# ALU.net
KiCad netlist of a schematic drawn in EAGLE
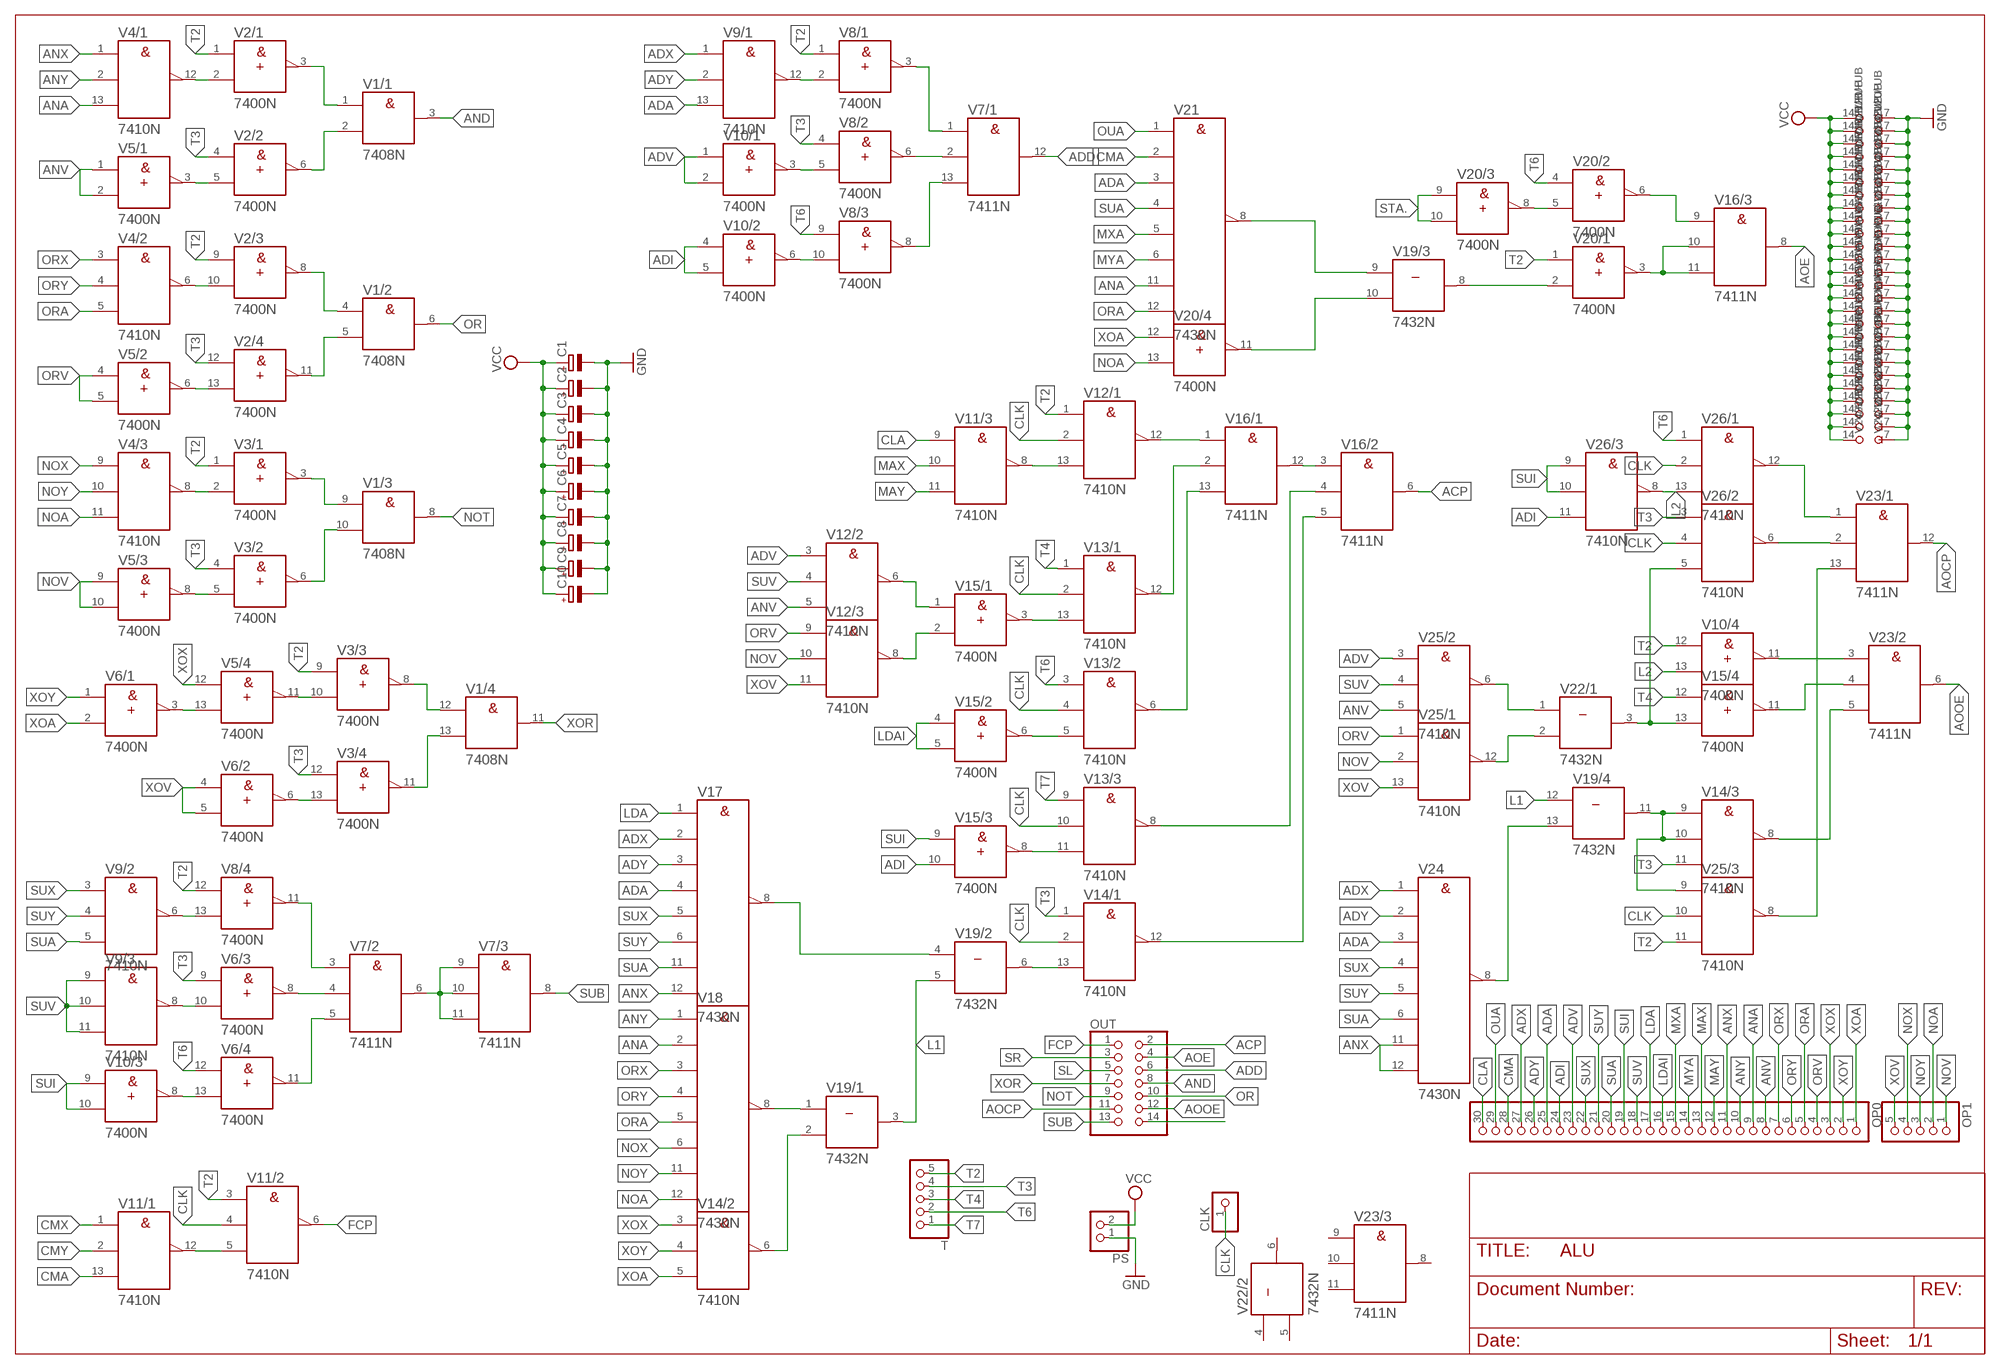
[diagram p0: schematic, sheet 1]

(export (version "E")
  (design (tool "Eeschema 10.0.6"))
  (components
    (comp (ref "C1")
      (value "CPOL-EUE2.5-6")
      (footprint "eagle-import:E2,5-6")
      (libsource (lib "eagle-import") (part "CPOL-EUE2.5-6"))
    )
    (comp (ref "C2")
      (value "CPOL-EUE2.5-6")
      (footprint "eagle-import:E2,5-6")
      (libsource (lib "eagle-import") (part "CPOL-EUE2.5-6"))
    )
    (comp (ref "C3")
      (value "CPOL-EUE2.5-6")
      (footprint "eagle-import:E2,5-6")
      (libsource (lib "eagle-import") (part "CPOL-EUE2.5-6"))
    )
    (comp (ref "C4")
      (value "CPOL-EUE2.5-6")
      (footprint "eagle-import:E2,5-6")
      (libsource (lib "eagle-import") (part "CPOL-EUE2.5-6"))
    )
    (comp (ref "C5")
      (value "CPOL-EUE2.5-6")
      (footprint "eagle-import:E2,5-6")
      (libsource (lib "eagle-import") (part "CPOL-EUE2.5-6"))
    )
    (comp (ref "C6")
      (value "CPOL-EUE2.5-6")
      (footprint "eagle-import:E2,5-6")
      (libsource (lib "eagle-import") (part "CPOL-EUE2.5-6"))
    )
    (comp (ref "C7")
      (value "CPOL-EUE2.5-6")
      (footprint "eagle-import:E2,5-6")
      (libsource (lib "eagle-import") (part "CPOL-EUE2.5-6"))
    )
    (comp (ref "C8")
      (value "CPOL-EUE2.5-6")
      (footprint "eagle-import:E2,5-6")
      (libsource (lib "eagle-import") (part "CPOL-EUE2.5-6"))
    )
    (comp (ref "C9")
      (value "CPOL-EUE2.5-6")
      (footprint "eagle-import:E2,5-6")
      (libsource (lib "eagle-import") (part "CPOL-EUE2.5-6"))
    )
    (comp (ref "C10")
      (value "CPOL-EUE2.5-6")
      (footprint "eagle-import:E2,5-6")
      (libsource (lib "eagle-import") (part "CPOL-EUE2.5-6"))
    )
    (comp (ref "CLK")
      (value "PINHD-1X1")
      (footprint "eagle-import:1X01")
      (libsource (lib "eagle-import") (part "PINHD-1X1"))
    )
    (comp (ref "OP0")
      (value "PINHD-1X30")
      (footprint "eagle-import:1X30")
      (libsource (lib "eagle-import") (part "PINHD-1X30"))
    )
    (comp (ref "OP1")
      (value "PINHD-1X5")
      (footprint "eagle-import:1X05")
      (libsource (lib "eagle-import") (part "PINHD-1X5"))
    )
    (comp (ref "OUT")
      (value "PINHD-2X7")
      (footprint "eagle-import:2X07")
      (libsource (lib "eagle-import") (part "PINHD-2X7"))
    )
    (comp (ref "PS")
      (value "PINHD-1X2")
      (footprint "eagle-import:1X02")
      (libsource (lib "eagle-import") (part "PINHD-1X2"))
    )
    (comp (ref "T")
      (value "PINHD-1X5")
      (footprint "eagle-import:1X05")
      (libsource (lib "eagle-import") (part "PINHD-1X5"))
    )
    (comp (ref "V1")
      (value "7408N")
      (footprint "eagle-import:DIL14")
      (libsource (lib "eagle-import") (part "7408N"))
    )
    (comp (ref "V2")
      (value "7400N")
      (footprint "eagle-import:DIL14")
      (libsource (lib "eagle-import") (part "7400N"))
    )
    (comp (ref "V3")
      (value "7400N")
      (footprint "eagle-import:DIL14")
      (libsource (lib "eagle-import") (part "7400N"))
    )
    (comp (ref "V4")
      (value "7410N")
      (footprint "eagle-import:DIL14")
      (libsource (lib "eagle-import") (part "7410N"))
    )
    (comp (ref "V5")
      (value "7400N")
      (footprint "eagle-import:DIL14")
      (libsource (lib "eagle-import") (part "7400N"))
    )
    (comp (ref "V6")
      (value "7400N")
      (footprint "eagle-import:DIL14")
      (libsource (lib "eagle-import") (part "7400N"))
    )
    (comp (ref "V7")
      (value "7411N")
      (footprint "eagle-import:DIL14")
      (libsource (lib "eagle-import") (part "7411N"))
    )
    (comp (ref "V8")
      (value "7400N")
      (footprint "eagle-import:DIL14")
      (libsource (lib "eagle-import") (part "7400N"))
    )
    (comp (ref "V9")
      (value "7410N")
      (footprint "eagle-import:DIL14")
      (libsource (lib "eagle-import") (part "7410N"))
    )
    (comp (ref "V10")
      (value "7400N")
      (footprint "eagle-import:DIL14")
      (libsource (lib "eagle-import") (part "7400N"))
    )
    (comp (ref "V11")
      (value "7410N")
      (footprint "eagle-import:DIL14")
      (libsource (lib "eagle-import") (part "7410N"))
    )
    (comp (ref "V12")
      (value "7410N")
      (footprint "eagle-import:DIL14")
      (libsource (lib "eagle-import") (part "7410N"))
    )
    (comp (ref "V13")
      (value "7410N")
      (footprint "eagle-import:DIL14")
      (libsource (lib "eagle-import") (part "7410N"))
    )
    (comp (ref "V14")
      (value "7410N")
      (footprint "eagle-import:DIL14")
      (libsource (lib "eagle-import") (part "7410N"))
    )
    (comp (ref "V15")
      (value "7400N")
      (footprint "eagle-import:DIL14")
      (libsource (lib "eagle-import") (part "7400N"))
    )
    (comp (ref "V16")
      (value "7411N")
      (footprint "eagle-import:DIL14")
      (libsource (lib "eagle-import") (part "7411N"))
    )
    (comp (ref "V17")
      (value "7430N")
      (footprint "eagle-import:DIL14")
      (libsource (lib "eagle-import") (part "7430N"))
    )
    (comp (ref "V18")
      (value "7430N")
      (footprint "eagle-import:DIL14")
      (libsource (lib "eagle-import") (part "7430N"))
    )
    (comp (ref "V19")
      (value "7432N")
      (footprint "eagle-import:DIL14")
      (libsource (lib "eagle-import") (part "7432N"))
    )
    (comp (ref "V20")
      (value "7400N")
      (footprint "eagle-import:DIL14")
      (libsource (lib "eagle-import") (part "7400N"))
    )
    (comp (ref "V21")
      (value "7430N")
      (footprint "eagle-import:DIL14")
      (libsource (lib "eagle-import") (part "7430N"))
    )
    (comp (ref "V22")
      (value "7432N")
      (footprint "eagle-import:DIL14")
      (libsource (lib "eagle-import") (part "7432N"))
    )
    (comp (ref "V23")
      (value "7411N")
      (footprint "eagle-import:DIL14")
      (libsource (lib "eagle-import") (part "7411N"))
    )
    (comp (ref "V24")
      (value "7430N")
      (footprint "eagle-import:DIL14")
      (libsource (lib "eagle-import") (part "7430N"))
    )
    (comp (ref "V25")
      (value "7410N")
      (footprint "eagle-import:DIL14")
      (libsource (lib "eagle-import") (part "7410N"))
    )
    (comp (ref "V26")
      (value "7410N")
      (footprint "eagle-import:DIL14")
      (libsource (lib "eagle-import") (part "7410N"))
    )
  )
  (nets
    (net (code "1") (name "ACP") (class "Default")
      (node (ref "OUT") (pin "2") (pinfunction "2_2") (pintype "passive"))
      (node (ref "V16") (pin "6") (pinfunction "Y_6") (pintype "output"))
    )
    (net (code "2") (name "ADA") (class "Default")
      (node (ref "OP0") (pin "25") (pinfunction "25_25") (pintype "passive"))
      (node (ref "V17") (pin "4") (pinfunction "D_4") (pintype "input"))
      (node (ref "V21") (pin "3") (pinfunction "C_3") (pintype "input"))
      (node (ref "V24") (pin "3") (pinfunction "C_3") (pintype "input"))
      (node (ref "V9") (pin "13") (pinfunction "C_13") (pintype "input"))
    )
    (net (code "3") (name "ADD") (class "Default")
      (node (ref "OUT") (pin "6") (pinfunction "6_6") (pintype "passive"))
      (node (ref "V7") (pin "12") (pinfunction "Y_12") (pintype "output"))
    )
    (net (code "4") (name "ADI") (class "Default")
      (node (ref "OP0") (pin "24") (pinfunction "24_24") (pintype "passive"))
      (node (ref "V10") (pin "4") (pinfunction "A_4") (pintype "input"))
      (node (ref "V10") (pin "5") (pinfunction "B_5") (pintype "input"))
      (node (ref "V15") (pin "10") (pinfunction "B_10") (pintype "input"))
      (node (ref "V26") (pin "11") (pinfunction "C_11") (pintype "input"))
    )
    (net (code "5") (name "ADV") (class "Default")
      (node (ref "OP0") (pin "23") (pinfunction "23_23") (pintype "passive"))
      (node (ref "V10") (pin "1") (pinfunction "A_1") (pintype "input"))
      (node (ref "V10") (pin "2") (pinfunction "B_2") (pintype "input"))
      (node (ref "V12") (pin "3") (pinfunction "A_3") (pintype "input"))
      (node (ref "V25") (pin "3") (pinfunction "A_3") (pintype "input"))
    )
    (net (code "6") (name "ADX") (class "Default")
      (node (ref "OP0") (pin "27") (pinfunction "27_27") (pintype "passive"))
      (node (ref "V17") (pin "2") (pinfunction "B_2") (pintype "input"))
      (node (ref "V24") (pin "1") (pinfunction "A_1") (pintype "input"))
      (node (ref "V9") (pin "1") (pinfunction "A_1") (pintype "input"))
    )
    (net (code "7") (name "ADY") (class "Default")
      (node (ref "OP0") (pin "26") (pinfunction "26_26") (pintype "passive"))
      (node (ref "V17") (pin "3") (pinfunction "C_3") (pintype "input"))
      (node (ref "V24") (pin "2") (pinfunction "B_2") (pintype "input"))
      (node (ref "V9") (pin "2") (pinfunction "B_2") (pintype "input"))
    )
    (net (code "8") (name "ANA") (class "Default")
      (node (ref "OP0") (pin "9") (pinfunction "9_9") (pintype "passive"))
      (node (ref "V18") (pin "2") (pinfunction "B_2") (pintype "input"))
      (node (ref "V21") (pin "11") (pinfunction "G_11") (pintype "input"))
      (node (ref "V4") (pin "13") (pinfunction "C_13") (pintype "input"))
    )
    (net (code "9") (name "AND") (class "Default")
      (node (ref "OUT") (pin "8") (pinfunction "8_8") (pintype "passive"))
      (node (ref "V1") (pin "3") (pinfunction "Y_3") (pintype "output"))
    )
    (net (code "10") (name "ANV") (class "Default")
      (node (ref "OP0") (pin "8") (pinfunction "8_8") (pintype "passive"))
      (node (ref "V12") (pin "5") (pinfunction "C_5") (pintype "input"))
      (node (ref "V25") (pin "5") (pinfunction "C_5") (pintype "input"))
      (node (ref "V5") (pin "1") (pinfunction "A_1") (pintype "input"))
      (node (ref "V5") (pin "2") (pinfunction "B_2") (pintype "input"))
    )
    (net (code "11") (name "ANX") (class "Default")
      (node (ref "OP0") (pin "11") (pinfunction "11_11") (pintype "passive"))
      (node (ref "V17") (pin "12") (pinfunction "H_12") (pintype "input"))
      (node (ref "V24") (pin "11") (pinfunction "G_11") (pintype "input"))
      (node (ref "V24") (pin "12") (pinfunction "H_12") (pintype "input"))
      (node (ref "V4") (pin "1") (pinfunction "A_1") (pintype "input"))
    )
    (net (code "12") (name "ANY") (class "Default")
      (node (ref "OP0") (pin "10") (pinfunction "10_10") (pintype "passive"))
      (node (ref "V18") (pin "1") (pinfunction "A_1") (pintype "input"))
      (node (ref "V4") (pin "2") (pinfunction "B_2") (pintype "input"))
    )
    (net (code "13") (name "AOCP") (class "Default")
      (node (ref "OUT") (pin "11") (pinfunction "11_11") (pintype "passive"))
      (node (ref "V23") (pin "12") (pinfunction "Y_12") (pintype "output"))
    )
    (net (code "14") (name "AOE") (class "Default")
      (node (ref "OUT") (pin "4") (pinfunction "4_4") (pintype "passive"))
      (node (ref "V16") (pin "8") (pinfunction "Y_8") (pintype "output"))
    )
    (net (code "15") (name "AOOE") (class "Default")
      (node (ref "OUT") (pin "12") (pinfunction "12_12") (pintype "passive"))
      (node (ref "V23") (pin "6") (pinfunction "Y_6") (pintype "output"))
    )
    (net (code "16") (name "CLA") (class "Default")
      (node (ref "OP0") (pin "30") (pinfunction "30_30") (pintype "passive"))
      (node (ref "V11") (pin "9") (pinfunction "A_9") (pintype "input"))
    )
    (net (code "17") (name "CLK") (class "Default")
      (node (ref "CLK") (pin "1") (pinfunction "1_1") (pintype "passive"))
      (node (ref "V11") (pin "4") (pinfunction "B_4") (pintype "input"))
      (node (ref "V12") (pin "2") (pinfunction "B_2") (pintype "input"))
      (node (ref "V13") (pin "10") (pinfunction "B_10") (pintype "input"))
      (node (ref "V13") (pin "2") (pinfunction "B_2") (pintype "input"))
      (node (ref "V13") (pin "4") (pinfunction "B_4") (pintype "input"))
      (node (ref "V14") (pin "2") (pinfunction "B_2") (pintype "input"))
      (node (ref "V25") (pin "10") (pinfunction "B_10") (pintype "input"))
      (node (ref "V26") (pin "2") (pinfunction "B_2") (pintype "input"))
      (node (ref "V26") (pin "4") (pinfunction "B_4") (pintype "input"))
    )
    (net (code "18") (name "CMA") (class "Default")
      (node (ref "OP0") (pin "28") (pinfunction "28_28") (pintype "passive"))
      (node (ref "V11") (pin "13") (pinfunction "C_13") (pintype "input"))
      (node (ref "V21") (pin "2") (pinfunction "B_2") (pintype "input"))
    )
    (net (code "19") (name "CMX") (class "Default")
      (node (ref "V11") (pin "1") (pinfunction "A_1") (pintype "input"))
    )
    (net (code "20") (name "CMY") (class "Default")
      (node (ref "V11") (pin "2") (pinfunction "B_2") (pintype "input"))
    )
    (net (code "21") (name "FCP") (class "Default")
      (node (ref "OUT") (pin "1") (pinfunction "1_1") (pintype "passive"))
      (node (ref "V11") (pin "6") (pinfunction "Y_6") (pintype "output"))
    )
    (net (code "22") (name "GND") (class "Default")
      (node (ref "C1") (pin "-") (pinfunction "-_-") (pintype "passive"))
      (node (ref "C10") (pin "-") (pinfunction "-_-") (pintype "passive"))
      (node (ref "C2") (pin "-") (pinfunction "-_-") (pintype "passive"))
      (node (ref "C3") (pin "-") (pinfunction "-_-") (pintype "passive"))
      (node (ref "C4") (pin "-") (pinfunction "-_-") (pintype "passive"))
      (node (ref "C5") (pin "-") (pinfunction "-_-") (pintype "passive"))
      (node (ref "C6") (pin "-") (pinfunction "-_-") (pintype "passive"))
      (node (ref "C7") (pin "-") (pinfunction "-_-") (pintype "passive"))
      (node (ref "C8") (pin "-") (pinfunction "-_-") (pintype "passive"))
      (node (ref "C9") (pin "-") (pinfunction "-_-") (pintype "passive"))
      (node (ref "PS") (pin "1") (pinfunction "1_1") (pintype "passive"))
      (node (ref "V1") (pin "7") (pinfunction "-UB_7") (pintype "power_in"))
      (node (ref "V10") (pin "7") (pinfunction "-UB_7") (pintype "power_in"))
      (node (ref "V11") (pin "7") (pinfunction "-UB_7") (pintype "power_in"))
      (node (ref "V12") (pin "7") (pinfunction "-UB_7") (pintype "power_in"))
      (node (ref "V13") (pin "7") (pinfunction "-UB_7") (pintype "power_in"))
      (node (ref "V14") (pin "7") (pinfunction "-UB_7") (pintype "power_in"))
      (node (ref "V15") (pin "7") (pinfunction "-UB_7") (pintype "power_in"))
      (node (ref "V16") (pin "7") (pinfunction "-UB_7") (pintype "power_in"))
      (node (ref "V17") (pin "7") (pinfunction "-UB_7") (pintype "power_in"))
      (node (ref "V18") (pin "7") (pinfunction "-UB_7") (pintype "power_in"))
      (node (ref "V19") (pin "7") (pinfunction "-UB_7") (pintype "power_in"))
      (node (ref "V2") (pin "7") (pinfunction "-UB_7") (pintype "power_in"))
      (node (ref "V20") (pin "7") (pinfunction "-UB_7") (pintype "power_in"))
      (node (ref "V21") (pin "7") (pinfunction "-UB_7") (pintype "power_in"))
      (node (ref "V22") (pin "7") (pinfunction "-UB_7") (pintype "power_in"))
      (node (ref "V23") (pin "7") (pinfunction "-UB_7") (pintype "power_in"))
      (node (ref "V24") (pin "7") (pinfunction "-UB_7") (pintype "power_in"))
      (node (ref "V25") (pin "7") (pinfunction "-UB_7") (pintype "power_in"))
      (node (ref "V26") (pin "7") (pinfunction "-UB_7") (pintype "power_in"))
      (node (ref "V3") (pin "7") (pinfunction "-UB_7") (pintype "power_in"))
      (node (ref "V4") (pin "7") (pinfunction "-UB_7") (pintype "power_in"))
      (node (ref "V5") (pin "7") (pinfunction "-UB_7") (pintype "power_in"))
      (node (ref "V6") (pin "7") (pinfunction "-UB_7") (pintype "power_in"))
      (node (ref "V7") (pin "7") (pinfunction "-UB_7") (pintype "power_in"))
      (node (ref "V8") (pin "7") (pinfunction "-UB_7") (pintype "power_in"))
      (node (ref "V9") (pin "7") (pinfunction "-UB_7") (pintype "power_in"))
    )
    (net (code "23") (name "L1") (class "Default")
      (node (ref "V19") (pin "12") (pinfunction "A_12") (pintype "input"))
      (node (ref "V19") (pin "3") (pinfunction "Y_3") (pintype "output"))
      (node (ref "V19") (pin "5") (pinfunction "B_5") (pintype "input"))
    )
    (net (code "24") (name "L2") (class "Default")
      (node (ref "V10") (pin "13") (pinfunction "B_13") (pintype "input"))
      (node (ref "V26") (pin "13") (pinfunction "C_13") (pintype "input"))
      (node (ref "V26") (pin "8") (pinfunction "Y_8") (pintype "output"))
    )
    (net (code "25") (name "LDA") (class "Default")
      (node (ref "OP0") (pin "17") (pinfunction "17_17") (pintype "passive"))
      (node (ref "V17") (pin "1") (pinfunction "A_1") (pintype "input"))
    )
    (net (code "26") (name "LDAI") (class "Default")
      (node (ref "OP0") (pin "16") (pinfunction "16_16") (pintype "passive"))
      (node (ref "V15") (pin "4") (pinfunction "A_4") (pintype "input"))
      (node (ref "V15") (pin "5") (pinfunction "B_5") (pintype "input"))
    )
    (net (code "27") (name "MAX") (class "Default")
      (node (ref "OP0") (pin "13") (pinfunction "13_13") (pintype "passive"))
      (node (ref "V11") (pin "10") (pinfunction "B_10") (pintype "input"))
    )
    (net (code "28") (name "MAY") (class "Default")
      (node (ref "OP0") (pin "12") (pinfunction "12_12") (pintype "passive"))
      (node (ref "V11") (pin "11") (pinfunction "C_11") (pintype "input"))
    )
    (net (code "29") (name "MXA") (class "Default")
      (node (ref "OP0") (pin "15") (pinfunction "15_15") (pintype "passive"))
      (node (ref "V21") (pin "5") (pinfunction "E_5") (pintype "input"))
    )
    (net (code "30") (name "MYA") (class "Default")
      (node (ref "OP0") (pin "14") (pinfunction "14_14") (pintype "passive"))
      (node (ref "V21") (pin "6") (pinfunction "F_6") (pintype "input"))
    )
    (net (code "31") (name "NOA") (class "Default")
      (node (ref "OP1") (pin "2") (pinfunction "2_2") (pintype "passive"))
      (node (ref "V18") (pin "12") (pinfunction "H_12") (pintype "input"))
      (node (ref "V20") (pin "13") (pinfunction "B_13") (pintype "input"))
      (node (ref "V4") (pin "11") (pinfunction "C_11") (pintype "input"))
    )
    (net (code "32") (name "NOT") (class "Default")
      (node (ref "OUT") (pin "9") (pinfunction "9_9") (pintype "passive"))
      (node (ref "V1") (pin "8") (pinfunction "Y_8") (pintype "output"))
    )
    (net (code "33") (name "NOV") (class "Default")
      (node (ref "OP1") (pin "1") (pinfunction "1_1") (pintype "passive"))
      (node (ref "V12") (pin "10") (pinfunction "B_10") (pintype "input"))
      (node (ref "V25") (pin "2") (pinfunction "B_2") (pintype "input"))
      (node (ref "V5") (pin "10") (pinfunction "B_10") (pintype "input"))
      (node (ref "V5") (pin "9") (pinfunction "A_9") (pintype "input"))
    )
    (net (code "34") (name "NOX") (class "Default")
      (node (ref "OP1") (pin "4") (pinfunction "4_4") (pintype "passive"))
      (node (ref "V18") (pin "6") (pinfunction "F_6") (pintype "input"))
      (node (ref "V4") (pin "9") (pinfunction "A_9") (pintype "input"))
    )
    (net (code "35") (name "NOY") (class "Default")
      (node (ref "OP1") (pin "3") (pinfunction "3_3") (pintype "passive"))
      (node (ref "V18") (pin "11") (pinfunction "G_11") (pintype "input"))
      (node (ref "V4") (pin "10") (pinfunction "B_10") (pintype "input"))
    )
    (net (code "36") (name "Net-(V1C-A)") (class "Default")
      (node (ref "V1") (pin "1") (pinfunction "A_1") (pintype "input"))
      (node (ref "V2") (pin "3") (pinfunction "Y_3") (pintype "output"))
    )
    (net (code "37") (name "Net-(V1C-B)") (class "Default")
      (node (ref "V1") (pin "2") (pinfunction "B_2") (pintype "input"))
      (node (ref "V2") (pin "6") (pinfunction "Y_6") (pintype "output"))
    )
    (net (code "38") (name "Net-(V1D-A)") (class "Default")
      (node (ref "V1") (pin "4") (pinfunction "A_4") (pintype "input"))
      (node (ref "V2") (pin "8") (pinfunction "Y_8") (pintype "output"))
    )
    (net (code "39") (name "Net-(V1D-B)") (class "Default")
      (node (ref "V1") (pin "5") (pinfunction "B_5") (pintype "input"))
      (node (ref "V2") (pin "11") (pinfunction "Y_11") (pintype "output"))
    )
    (net (code "40") (name "Net-(V1E-A)") (class "Default")
      (node (ref "V1") (pin "9") (pinfunction "A_9") (pintype "input"))
      (node (ref "V3") (pin "3") (pinfunction "Y_3") (pintype "output"))
    )
    (net (code "41") (name "Net-(V1E-B)") (class "Default")
      (node (ref "V1") (pin "10") (pinfunction "B_10") (pintype "input"))
      (node (ref "V3") (pin "6") (pinfunction "Y_6") (pintype "output"))
    )
    (net (code "42") (name "Net-(V1F-A)") (class "Default")
      (node (ref "V1") (pin "12") (pinfunction "A_12") (pintype "input"))
      (node (ref "V3") (pin "8") (pinfunction "Y_8") (pintype "output"))
    )
    (net (code "43") (name "Net-(V1F-B)") (class "Default")
      (node (ref "V1") (pin "13") (pinfunction "B_13") (pintype "input"))
      (node (ref "V3") (pin "11") (pinfunction "Y_11") (pintype "output"))
    )
    (net (code "44") (name "Net-(V2C-B)") (class "Default")
      (node (ref "V2") (pin "2") (pinfunction "B_2") (pintype "input"))
      (node (ref "V4") (pin "12") (pinfunction "Y_12") (pintype "output"))
    )
    (net (code "45") (name "Net-(V2D-B)") (class "Default")
      (node (ref "V2") (pin "5") (pinfunction "B_5") (pintype "input"))
      (node (ref "V5") (pin "3") (pinfunction "Y_3") (pintype "output"))
    )
    (net (code "46") (name "Net-(V2E-B)") (class "Default")
      (node (ref "V2") (pin "10") (pinfunction "B_10") (pintype "input"))
      (node (ref "V4") (pin "6") (pinfunction "Y_6") (pintype "output"))
    )
    (net (code "47") (name "Net-(V2F-B)") (class "Default")
      (node (ref "V2") (pin "13") (pinfunction "B_13") (pintype "input"))
      (node (ref "V5") (pin "6") (pinfunction "Y_6") (pintype "output"))
    )
    (net (code "48") (name "Net-(V3C-B)") (class "Default")
      (node (ref "V3") (pin "2") (pinfunction "B_2") (pintype "input"))
      (node (ref "V4") (pin "8") (pinfunction "Y_8") (pintype "output"))
    )
    (net (code "49") (name "Net-(V3D-B)") (class "Default")
      (node (ref "V3") (pin "5") (pinfunction "B_5") (pintype "input"))
      (node (ref "V5") (pin "8") (pinfunction "Y_8") (pintype "output"))
    )
    (net (code "50") (name "Net-(V3E-B)") (class "Default")
      (node (ref "V3") (pin "10") (pinfunction "B_10") (pintype "input"))
      (node (ref "V5") (pin "11") (pinfunction "Y_11") (pintype "output"))
    )
    (net (code "51") (name "Net-(V3F-B)") (class "Default")
      (node (ref "V3") (pin "13") (pinfunction "B_13") (pintype "input"))
      (node (ref "V6") (pin "6") (pinfunction "Y_6") (pintype "output"))
    )
    (net (code "52") (name "Net-(V5F-B)") (class "Default")
      (node (ref "V5") (pin "13") (pinfunction "B_13") (pintype "input"))
      (node (ref "V6") (pin "3") (pinfunction "Y_3") (pintype "output"))
    )
    (net (code "53") (name "Net-(V6E-B)") (class "Default")
      (node (ref "V6") (pin "10") (pinfunction "B_10") (pintype "input"))
      (node (ref "V9") (pin "8") (pinfunction "Y_8") (pintype "output"))
    )
    (net (code "54") (name "Net-(V6E-Y)") (class "Default")
      (node (ref "V6") (pin "8") (pinfunction "Y_8") (pintype "output"))
      (node (ref "V7") (pin "4") (pinfunction "B_4") (pintype "input"))
    )
    (net (code "55") (name "Net-(V6F-Y)") (class "Default")
      (node (ref "V6") (pin "11") (pinfunction "Y_11") (pintype "output"))
      (node (ref "V7") (pin "5") (pinfunction "C_5") (pintype "input"))
    )
    (net (code "56") (name "Net-(V7C-A)") (class "Default")
      (node (ref "V7") (pin "1") (pinfunction "A_1") (pintype "input"))
      (node (ref "V8") (pin "3") (pinfunction "Y_3") (pintype "output"))
    )
    (net (code "57") (name "Net-(V7C-B)") (class "Default")
      (node (ref "V7") (pin "2") (pinfunction "B_2") (pintype "input"))
      (node (ref "V8") (pin "6") (pinfunction "Y_6") (pintype "output"))
    )
    (net (code "58") (name "Net-(V7C-C)") (class "Default")
      (node (ref "V7") (pin "13") (pinfunction "C_13") (pintype "input"))
      (node (ref "V8") (pin "8") (pinfunction "Y_8") (pintype "output"))
    )
    (net (code "59") (name "Net-(V7D-A)") (class "Default")
      (node (ref "V7") (pin "3") (pinfunction "A_3") (pintype "input"))
      (node (ref "V8") (pin "11") (pinfunction "Y_11") (pintype "output"))
    )
    (net (code "60") (name "Net-(V7D-Y)") (class "Default")
      (node (ref "V7") (pin "10") (pinfunction "B_10") (pintype "input"))
      (node (ref "V7") (pin "11") (pinfunction "C_11") (pintype "input"))
      (node (ref "V7") (pin "6") (pinfunction "Y_6") (pintype "output"))
      (node (ref "V7") (pin "9") (pinfunction "A_9") (pintype "input"))
    )
    (net (code "61") (name "Net-(V8C-B)") (class "Default")
      (node (ref "V8") (pin "2") (pinfunction "B_2") (pintype "input"))
      (node (ref "V9") (pin "12") (pinfunction "Y_12") (pintype "output"))
    )
    (net (code "62") (name "Net-(V8F-B)") (class "Default")
      (node (ref "V8") (pin "13") (pinfunction "B_13") (pintype "input"))
      (node (ref "V9") (pin "6") (pinfunction "Y_6") (pintype "output"))
    )
    (net (code "63") (name "Net-(V10C-Y)") (class "Default")
      (node (ref "V10") (pin "3") (pinfunction "Y_3") (pintype "output"))
      (node (ref "V8") (pin "5") (pinfunction "B_5") (pintype "input"))
    )
    (net (code "64") (name "Net-(V10D-Y)") (class "Default")
      (node (ref "V10") (pin "6") (pinfunction "Y_6") (pintype "output"))
      (node (ref "V8") (pin "10") (pinfunction "B_10") (pintype "input"))
    )
    (net (code "65") (name "Net-(V10E-Y)") (class "Default")
      (node (ref "V10") (pin "8") (pinfunction "Y_8") (pintype "output"))
      (node (ref "V6") (pin "13") (pinfunction "B_13") (pintype "input"))
    )
    (net (code "66") (name "Net-(V10F-Y)") (class "Default")
      (node (ref "V10") (pin "11") (pinfunction "Y_11") (pintype "output"))
      (node (ref "V23") (pin "3") (pinfunction "A_3") (pintype "input"))
    )
    (net (code "67") (name "Net-(V11C-Y)") (class "Default")
      (node (ref "V11") (pin "12") (pinfunction "Y_12") (pintype "output"))
      (node (ref "V11") (pin "5") (pinfunction "C_5") (pintype "input"))
    )
    (net (code "68") (name "Net-(V11E-Y)") (class "Default")
      (node (ref "V11") (pin "8") (pinfunction "Y_8") (pintype "output"))
      (node (ref "V12") (pin "13") (pinfunction "C_13") (pintype "input"))
    )
    (net (code "69") (name "Net-(V12C-Y)") (class "Default")
      (node (ref "V12") (pin "12") (pinfunction "Y_12") (pintype "output"))
      (node (ref "V16") (pin "1") (pinfunction "A_1") (pintype "input"))
    )
    (net (code "70") (name "Net-(V12D-Y)") (class "Default")
      (node (ref "V12") (pin "6") (pinfunction "Y_6") (pintype "output"))
      (node (ref "V15") (pin "1") (pinfunction "A_1") (pintype "input"))
    )
    (net (code "71") (name "Net-(V12E-Y)") (class "Default")
      (node (ref "V12") (pin "8") (pinfunction "Y_8") (pintype "output"))
      (node (ref "V15") (pin "2") (pinfunction "B_2") (pintype "input"))
    )
    (net (code "72") (name "Net-(V13C-C)") (class "Default")
      (node (ref "V13") (pin "13") (pinfunction "C_13") (pintype "input"))
      (node (ref "V15") (pin "3") (pinfunction "Y_3") (pintype "output"))
    )
    (net (code "73") (name "Net-(V13C-Y)") (class "Default")
      (node (ref "V13") (pin "12") (pinfunction "Y_12") (pintype "output"))
      (node (ref "V16") (pin "2") (pinfunction "B_2") (pintype "input"))
    )
    (net (code "74") (name "Net-(V13D-C)") (class "Default")
      (node (ref "V13") (pin "5") (pinfunction "C_5") (pintype "input"))
      (node (ref "V15") (pin "6") (pinfunction "Y_6") (pintype "output"))
    )
    (net (code "75") (name "Net-(V13D-Y)") (class "Default")
      (node (ref "V13") (pin "6") (pinfunction "Y_6") (pintype "output"))
      (node (ref "V16") (pin "13") (pinfunction "C_13") (pintype "input"))
    )
    (net (code "76") (name "Net-(V13E-C)") (class "Default")
      (node (ref "V13") (pin "11") (pinfunction "C_11") (pintype "input"))
      (node (ref "V15") (pin "8") (pinfunction "Y_8") (pintype "output"))
    )
    (net (code "77") (name "Net-(V13E-Y)") (class "Default")
      (node (ref "V13") (pin "8") (pinfunction "Y_8") (pintype "output"))
      (node (ref "V16") (pin "4") (pinfunction "B_4") (pintype "input"))
    )
    (net (code "78") (name "Net-(V14C-C)") (class "Default")
      (node (ref "V14") (pin "13") (pinfunction "C_13") (pintype "input"))
      (node (ref "V19") (pin "6") (pinfunction "Y_6") (pintype "output"))
    )
    (net (code "79") (name "Net-(V14C-Y)") (class "Default")
      (node (ref "V14") (pin "12") (pinfunction "Y_12") (pintype "output"))
      (node (ref "V16") (pin "5") (pinfunction "C_5") (pintype "input"))
    )
    (net (code "80") (name "Net-(V14D-Y)") (class "Default")
      (node (ref "V14") (pin "6") (pinfunction "Y_6") (pintype "output"))
      (node (ref "V19") (pin "2") (pinfunction "B_2") (pintype "input"))
    )
    (net (code "81") (name "Net-(V14E-A)") (class "Default")
      (node (ref "V14") (pin "10") (pinfunction "B_10") (pintype "input"))
      (node (ref "V14") (pin "9") (pinfunction "A_9") (pintype "input"))
      (node (ref "V19") (pin "11") (pinfunction "Y_11") (pintype "output"))
      (node (ref "V25") (pin "9") (pinfunction "A_9") (pintype "input"))
    )
    (net (code "82") (name "Net-(V14E-Y)") (class "Default")
      (node (ref "V14") (pin "8") (pinfunction "Y_8") (pintype "output"))
      (node (ref "V23") (pin "5") (pinfunction "C_5") (pintype "input"))
    )
    (net (code "83") (name "Net-(V15F-B)") (class "Default")
      (node (ref "V15") (pin "13") (pinfunction "B_13") (pintype "input"))
      (node (ref "V22") (pin "3") (pinfunction "Y_3") (pintype "output"))
      (node (ref "V26") (pin "5") (pinfunction "C_5") (pintype "input"))
    )
    (net (code "84") (name "Net-(V15F-Y)") (class "Default")
      (node (ref "V15") (pin "11") (pinfunction "Y_11") (pintype "output"))
      (node (ref "V23") (pin "4") (pinfunction "B_4") (pintype "input"))
    )
    (net (code "85") (name "Net-(V16C-Y)") (class "Default")
      (node (ref "V16") (pin "12") (pinfunction "Y_12") (pintype "output"))
      (node (ref "V16") (pin "3") (pinfunction "A_3") (pintype "input"))
    )
    (net (code "86") (name "Net-(V16E-A)") (class "Default")
      (node (ref "V16") (pin "9") (pinfunction "A_9") (pintype "input"))
      (node (ref "V20") (pin "6") (pinfunction "Y_6") (pintype "output"))
    )
    (net (code "87") (name "Net-(V16E-B)") (class "Default")
      (node (ref "V16") (pin "10") (pinfunction "B_10") (pintype "input"))
      (node (ref "V16") (pin "11") (pinfunction "C_11") (pintype "input"))
      (node (ref "V20") (pin "3") (pinfunction "Y_3") (pintype "output"))
    )
    (net (code "88") (name "Net-(V17C-Y)") (class "Default")
      (node (ref "V17") (pin "8") (pinfunction "Y_8") (pintype "output"))
      (node (ref "V19") (pin "4") (pinfunction "A_4") (pintype "input"))
    )
    (net (code "89") (name "Net-(V18C-Y)") (class "Default")
      (node (ref "V18") (pin "8") (pinfunction "Y_8") (pintype "output"))
      (node (ref "V19") (pin "1") (pinfunction "A_1") (pintype "input"))
    )
    (net (code "90") (name "Net-(V19E-A)") (class "Default")
      (node (ref "V19") (pin "9") (pinfunction "A_9") (pintype "input"))
      (node (ref "V21") (pin "8") (pinfunction "Y_8") (pintype "output"))
    )
    (net (code "91") (name "Net-(V19E-B)") (class "Default")
      (node (ref "V19") (pin "10") (pinfunction "B_10") (pintype "input"))
      (node (ref "V20") (pin "11") (pinfunction "Y_11") (pintype "output"))
    )
    (net (code "92") (name "Net-(V19E-Y)") (class "Default")
      (node (ref "V19") (pin "8") (pinfunction "Y_8") (pintype "output"))
      (node (ref "V20") (pin "2") (pinfunction "B_2") (pintype "input"))
    )
    (net (code "93") (name "Net-(V19F-B)") (class "Default")
      (node (ref "V19") (pin "13") (pinfunction "B_13") (pintype "input"))
      (node (ref "V24") (pin "8") (pinfunction "Y_8") (pintype "output"))
    )
    (net (code "94") (name "Net-(V20D-B)") (class "Default")
      (node (ref "V20") (pin "5") (pinfunction "B_5") (pintype "input"))
      (node (ref "V20") (pin "8") (pinfunction "Y_8") (pintype "output"))
    )
    (net (code "95") (name "Net-(V22C-A)") (class "Default")
      (node (ref "V22") (pin "1") (pinfunction "A_1") (pintype "input"))
      (node (ref "V25") (pin "6") (pinfunction "Y_6") (pintype "output"))
    )
    (net (code "96") (name "Net-(V22C-B)") (class "Default")
      (node (ref "V22") (pin "2") (pinfunction "B_2") (pintype "input"))
      (node (ref "V25") (pin "12") (pinfunction "Y_12") (pintype "output"))
    )
    (net (code "97") (name "Net-(V23C-A)") (class "Default")
      (node (ref "V23") (pin "1") (pinfunction "A_1") (pintype "input"))
      (node (ref "V26") (pin "12") (pinfunction "Y_12") (pintype "output"))
    )
    (net (code "98") (name "Net-(V23C-B)") (class "Default")
      (node (ref "V23") (pin "2") (pinfunction "B_2") (pintype "input"))
      (node (ref "V26") (pin "6") (pinfunction "Y_6") (pintype "output"))
    )
    (net (code "99") (name "Net-(V23C-C)") (class "Default")
      (node (ref "V23") (pin "13") (pinfunction "C_13") (pintype "input"))
      (node (ref "V25") (pin "8") (pinfunction "Y_8") (pintype "output"))
    )
    (net (code "100") (name "OR") (class "Default")
      (node (ref "OUT") (pin "10") (pinfunction "10_10") (pintype "passive"))
      (node (ref "V1") (pin "6") (pinfunction "Y_6") (pintype "output"))
    )
    (net (code "101") (name "ORA") (class "Default")
      (node (ref "OP0") (pin "5") (pinfunction "5_5") (pintype "passive"))
      (node (ref "V18") (pin "5") (pinfunction "E_5") (pintype "input"))
      (node (ref "V21") (pin "12") (pinfunction "H_12") (pintype "input"))
      (node (ref "V4") (pin "5") (pinfunction "C_5") (pintype "input"))
    )
    (net (code "102") (name "ORV") (class "Default")
      (node (ref "OP0") (pin "4") (pinfunction "4_4") (pintype "passive"))
      (node (ref "V12") (pin "9") (pinfunction "A_9") (pintype "input"))
      (node (ref "V25") (pin "1") (pinfunction "A_1") (pintype "input"))
      (node (ref "V5") (pin "4") (pinfunction "A_4") (pintype "input"))
      (node (ref "V5") (pin "5") (pinfunction "B_5") (pintype "input"))
    )
    (net (code "103") (name "ORX") (class "Default")
      (node (ref "OP0") (pin "7") (pinfunction "7_7") (pintype "passive"))
      (node (ref "V18") (pin "3") (pinfunction "C_3") (pintype "input"))
      (node (ref "V4") (pin "3") (pinfunction "A_3") (pintype "input"))
    )
    (net (code "104") (name "ORY") (class "Default")
      (node (ref "OP0") (pin "6") (pinfunction "6_6") (pintype "passive"))
      (node (ref "V18") (pin "4") (pinfunction "D_4") (pintype "input"))
      (node (ref "V4") (pin "4") (pinfunction "B_4") (pintype "input"))
    )
    (net (code "105") (name "OUA") (class "Default")
      (node (ref "OP0") (pin "29") (pinfunction "29_29") (pintype "passive"))
      (node (ref "V21") (pin "1") (pinfunction "A_1") (pintype "input"))
    )
    (net (code "106") (name "SL") (class "Default")
      (node (ref "OUT") (pin "5") (pinfunction "5_5") (pintype "passive"))
    )
    (net (code "107") (name "SR") (class "Default")
      (node (ref "OUT") (pin "3") (pinfunction "3_3") (pintype "passive"))
    )
    (net (code "108") (name "STA.") (class "Default")
      (node (ref "V20") (pin "10") (pinfunction "B_10") (pintype "input"))
      (node (ref "V20") (pin "9") (pinfunction "A_9") (pintype "input"))
    )
    (net (code "109") (name "SUA") (class "Default")
      (node (ref "OP0") (pin "20") (pinfunction "20_20") (pintype "passive"))
      (node (ref "V17") (pin "11") (pinfunction "G_11") (pintype "input"))
      (node (ref "V21") (pin "4") (pinfunction "D_4") (pintype "input"))
      (node (ref "V24") (pin "6") (pinfunction "F_6") (pintype "input"))
      (node (ref "V9") (pin "5") (pinfunction "C_5") (pintype "input"))
    )
    (net (code "110") (name "SUB") (class "Default")
      (node (ref "OUT") (pin "13") (pinfunction "13_13") (pintype "passive"))
      (node (ref "V7") (pin "8") (pinfunction "Y_8") (pintype "output"))
    )
    (net (code "111") (name "SUI") (class "Default")
      (node (ref "OP0") (pin "19") (pinfunction "19_19") (pintype "passive"))
      (node (ref "V10") (pin "10") (pinfunction "B_10") (pintype "input"))
      (node (ref "V10") (pin "9") (pinfunction "A_9") (pintype "input"))
      (node (ref "V15") (pin "9") (pinfunction "A_9") (pintype "input"))
      (node (ref "V26") (pin "10") (pinfunction "B_10") (pintype "input"))
      (node (ref "V26") (pin "9") (pinfunction "A_9") (pintype "input"))
    )
    (net (code "112") (name "SUV") (class "Default")
      (node (ref "OP0") (pin "18") (pinfunction "18_18") (pintype "passive"))
      (node (ref "V12") (pin "4") (pinfunction "B_4") (pintype "input"))
      (node (ref "V25") (pin "4") (pinfunction "B_4") (pintype "input"))
      (node (ref "V9") (pin "10") (pinfunction "B_10") (pintype "input"))
      (node (ref "V9") (pin "11") (pinfunction "C_11") (pintype "input"))
      (node (ref "V9") (pin "9") (pinfunction "A_9") (pintype "input"))
    )
    (net (code "113") (name "SUX") (class "Default")
      (node (ref "OP0") (pin "22") (pinfunction "22_22") (pintype "passive"))
      (node (ref "V17") (pin "5") (pinfunction "E_5") (pintype "input"))
      (node (ref "V24") (pin "4") (pinfunction "D_4") (pintype "input"))
      (node (ref "V9") (pin "3") (pinfunction "A_3") (pintype "input"))
    )
    (net (code "114") (name "SUY") (class "Default")
      (node (ref "OP0") (pin "21") (pinfunction "21_21") (pintype "passive"))
      (node (ref "V17") (pin "6") (pinfunction "F_6") (pintype "input"))
      (node (ref "V24") (pin "5") (pinfunction "E_5") (pintype "input"))
      (node (ref "V9") (pin "4") (pinfunction "B_4") (pintype "input"))
    )
    (net (code "115") (name "T2") (class "Default")
      (node (ref "T") (pin "5") (pinfunction "5_5") (pintype "passive"))
      (node (ref "V10") (pin "12") (pinfunction "A_12") (pintype "input"))
      (node (ref "V11") (pin "3") (pinfunction "A_3") (pintype "input"))
      (node (ref "V12") (pin "1") (pinfunction "A_1") (pintype "input"))
      (node (ref "V2") (pin "1") (pinfunction "A_1") (pintype "input"))
      (node (ref "V2") (pin "9") (pinfunction "A_9") (pintype "input"))
      (node (ref "V20") (pin "1") (pinfunction "A_1") (pintype "input"))
      (node (ref "V25") (pin "11") (pinfunction "C_11") (pintype "input"))
      (node (ref "V3") (pin "1") (pinfunction "A_1") (pintype "input"))
      (node (ref "V3") (pin "9") (pinfunction "A_9") (pintype "input"))
      (node (ref "V8") (pin "1") (pinfunction "A_1") (pintype "input"))
      (node (ref "V8") (pin "12") (pinfunction "A_12") (pintype "input"))
    )
    (net (code "116") (name "T3") (class "Default")
      (node (ref "T") (pin "4") (pinfunction "4_4") (pintype "passive"))
      (node (ref "V14") (pin "1") (pinfunction "A_1") (pintype "input"))
      (node (ref "V14") (pin "11") (pinfunction "C_11") (pintype "input"))
      (node (ref "V2") (pin "12") (pinfunction "A_12") (pintype "input"))
      (node (ref "V2") (pin "4") (pinfunction "A_4") (pintype "input"))
      (node (ref "V26") (pin "3") (pinfunction "A_3") (pintype "input"))
      (node (ref "V3") (pin "12") (pinfunction "A_12") (pintype "input"))
      (node (ref "V3") (pin "4") (pinfunction "A_4") (pintype "input"))
      (node (ref "V6") (pin "9") (pinfunction "A_9") (pintype "input"))
      (node (ref "V8") (pin "4") (pinfunction "A_4") (pintype "input"))
    )
    (net (code "117") (name "T4") (class "Default")
      (node (ref "T") (pin "3") (pinfunction "3_3") (pintype "passive"))
      (node (ref "V13") (pin "1") (pinfunction "A_1") (pintype "input"))
      (node (ref "V15") (pin "12") (pinfunction "A_12") (pintype "input"))
    )
    (net (code "118") (name "T6") (class "Default")
      (node (ref "T") (pin "2") (pinfunction "2_2") (pintype "passive"))
      (node (ref "V13") (pin "3") (pinfunction "A_3") (pintype "input"))
      (node (ref "V20") (pin "4") (pinfunction "A_4") (pintype "input"))
      (node (ref "V26") (pin "1") (pinfunction "A_1") (pintype "input"))
      (node (ref "V6") (pin "12") (pinfunction "A_12") (pintype "input"))
      (node (ref "V8") (pin "9") (pinfunction "A_9") (pintype "input"))
    )
    (net (code "119") (name "T7") (class "Default")
      (node (ref "T") (pin "1") (pinfunction "1_1") (pintype "passive"))
      (node (ref "V13") (pin "9") (pinfunction "A_9") (pintype "input"))
    )
    (net (code "120") (name "VCC") (class "Default")
      (node (ref "C1") (pin "+") (pinfunction "+_+") (pintype "passive"))
      (node (ref "C10") (pin "+") (pinfunction "+_+") (pintype "passive"))
      (node (ref "C2") (pin "+") (pinfunction "+_+") (pintype "passive"))
      (node (ref "C3") (pin "+") (pinfunction "+_+") (pintype "passive"))
      (node (ref "C4") (pin "+") (pinfunction "+_+") (pintype "passive"))
      (node (ref "C5") (pin "+") (pinfunction "+_+") (pintype "passive"))
      (node (ref "C6") (pin "+") (pinfunction "+_+") (pintype "passive"))
      (node (ref "C7") (pin "+") (pinfunction "+_+") (pintype "passive"))
      (node (ref "C8") (pin "+") (pinfunction "+_+") (pintype "passive"))
      (node (ref "C9") (pin "+") (pinfunction "+_+") (pintype "passive"))
      (node (ref "PS") (pin "2") (pinfunction "2_2") (pintype "passive"))
      (node (ref "V1") (pin "14") (pinfunction "+UB_14") (pintype "power_in"))
      (node (ref "V10") (pin "14") (pinfunction "+UB_14") (pintype "power_in"))
      (node (ref "V11") (pin "14") (pinfunction "+UB_14") (pintype "power_in"))
      (node (ref "V12") (pin "14") (pinfunction "+UB_14") (pintype "power_in"))
      (node (ref "V13") (pin "14") (pinfunction "+UB_14") (pintype "power_in"))
      (node (ref "V14") (pin "14") (pinfunction "+UB_14") (pintype "power_in"))
      (node (ref "V15") (pin "14") (pinfunction "+UB_14") (pintype "power_in"))
      (node (ref "V16") (pin "14") (pinfunction "+UB_14") (pintype "power_in"))
      (node (ref "V17") (pin "14") (pinfunction "+UB_14") (pintype "power_in"))
      (node (ref "V18") (pin "14") (pinfunction "+UB_14") (pintype "power_in"))
      (node (ref "V19") (pin "14") (pinfunction "+UB_14") (pintype "power_in"))
      (node (ref "V2") (pin "14") (pinfunction "+UB_14") (pintype "power_in"))
      (node (ref "V20") (pin "14") (pinfunction "+UB_14") (pintype "power_in"))
      (node (ref "V21") (pin "14") (pinfunction "+UB_14") (pintype "power_in"))
      (node (ref "V22") (pin "14") (pinfunction "+UB_14") (pintype "power_in"))
      (node (ref "V23") (pin "14") (pinfunction "+UB_14") (pintype "power_in"))
      (node (ref "V24") (pin "14") (pinfunction "+UB_14") (pintype "power_in"))
      (node (ref "V25") (pin "14") (pinfunction "+UB_14") (pintype "power_in"))
      (node (ref "V26") (pin "14") (pinfunction "+UB_14") (pintype "power_in"))
      (node (ref "V3") (pin "14") (pinfunction "+UB_14") (pintype "power_in"))
      (node (ref "V4") (pin "14") (pinfunction "+UB_14") (pintype "power_in"))
      (node (ref "V5") (pin "14") (pinfunction "+UB_14") (pintype "power_in"))
      (node (ref "V6") (pin "14") (pinfunction "+UB_14") (pintype "power_in"))
      (node (ref "V7") (pin "14") (pinfunction "+UB_14") (pintype "power_in"))
      (node (ref "V8") (pin "14") (pinfunction "+UB_14") (pintype "power_in"))
      (node (ref "V9") (pin "14") (pinfunction "+UB_14") (pintype "power_in"))
    )
    (net (code "121") (name "XOA") (class "Default")
      (node (ref "OP0") (pin "1") (pinfunction "1_1") (pintype "passive"))
      (node (ref "V14") (pin "5") (pinfunction "C_5") (pintype "input"))
      (node (ref "V20") (pin "12") (pinfunction "A_12") (pintype "input"))
      (node (ref "V6") (pin "2") (pinfunction "B_2") (pintype "input"))
    )
    (net (code "122") (name "XOR") (class "Default")
      (node (ref "OUT") (pin "7") (pinfunction "7_7") (pintype "passive"))
      (node (ref "V1") (pin "11") (pinfunction "Y_11") (pintype "output"))
    )
    (net (code "123") (name "XOV") (class "Default")
      (node (ref "OP1") (pin "5") (pinfunction "5_5") (pintype "passive"))
      (node (ref "V12") (pin "11") (pinfunction "C_11") (pintype "input"))
      (node (ref "V25") (pin "13") (pinfunction "C_13") (pintype "input"))
      (node (ref "V6") (pin "4") (pinfunction "A_4") (pintype "input"))
      (node (ref "V6") (pin "5") (pinfunction "B_5") (pintype "input"))
    )
    (net (code "124") (name "XOX") (class "Default")
      (node (ref "OP0") (pin "3") (pinfunction "3_3") (pintype "passive"))
      (node (ref "V14") (pin "3") (pinfunction "A_3") (pintype "input"))
      (node (ref "V5") (pin "12") (pinfunction "A_12") (pintype "input"))
    )
    (net (code "125") (name "XOY") (class "Default")
      (node (ref "OP0") (pin "2") (pinfunction "2_2") (pintype "passive"))
      (node (ref "V14") (pin "4") (pinfunction "B_4") (pintype "input"))
      (node (ref "V6") (pin "1") (pinfunction "A_1") (pintype "input"))
    )
    (net (code "126") (name "unconnected-(OUT-Pad14)") (class "Default")
      (node (ref "OUT") (pin "14") (pinfunction "14_14") (pintype "passive"))
    )
    (net (code "127") (name "unconnected-(V22D-A-Pad4)") (class "Default")
      (node (ref "V22") (pin "4") (pinfunction "A_4") (pintype "input"))
    )
    (net (code "128") (name "unconnected-(V22D-B-Pad5)") (class "Default")
      (node (ref "V22") (pin "5") (pinfunction "B_5") (pintype "input"))
    )
    (net (code "129") (name "unconnected-(V22D-Y-Pad6)") (class "Default")
      (node (ref "V22") (pin "6") (pinfunction "Y_6") (pintype "output"))
    )
    (net (code "130") (name "unconnected-(V23E-A-Pad9)") (class "Default")
      (node (ref "V23") (pin "9") (pinfunction "A_9") (pintype "input"))
    )
    (net (code "131") (name "unconnected-(V23E-B-Pad10)") (class "Default")
      (node (ref "V23") (pin "10") (pinfunction "B_10") (pintype "input"))
    )
    (net (code "132") (name "unconnected-(V23E-C-Pad11)") (class "Default")
      (node (ref "V23") (pin "11") (pinfunction "C_11") (pintype "input"))
    )
    (net (code "133") (name "unconnected-(V23E-Y-Pad8)") (class "Default")
      (node (ref "V23") (pin "8") (pinfunction "Y_8") (pintype "output"))
    )
  )
)
